# bug2.net
KiCad netlist of a schematic drawn in EAGLE
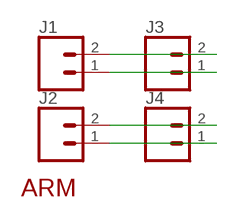
[diagram p0: schematic, sheet 1]

(export (version "E")
  (design (tool "Eeschema 10.0.6"))
  (components
    (comp (ref "J1")
      (value "CONN_02LOCK")
      (footprint "eagle-import:1X02_LOCK")
      (libsource (lib "eagle-import") (part "CONN_02LOCK"))
    )
    (comp (ref "J2")
      (value "CONN_02LOCK")
      (footprint "eagle-import:1X02_LOCK")
      (libsource (lib "eagle-import") (part "CONN_02LOCK"))
    )
    (comp (ref "J3")
      (value "CONN_02LOCK")
      (footprint "eagle-import:1X02_LOCK")
      (libsource (lib "eagle-import") (part "CONN_02LOCK"))
    )
    (comp (ref "J4")
      (value "CONN_02LOCK")
      (footprint "eagle-import:1X02_LOCK")
      (libsource (lib "eagle-import") (part "CONN_02LOCK"))
    )
    (comp (ref "U$1")
      (value "ARMBUG2")
      (footprint "eagle-import:BUG2")
      (libsource (lib "eagle-import") (part "ARMBUG2"))
    )
  )
  (nets
    (net (code "1") (name "Net-(J1-Pad1)") (class "Default")
      (node (ref "J1") (pin "1") (pinfunction "1_1") (pintype "passive"))
      (node (ref "J3") (pin "1") (pinfunction "1_1") (pintype "passive"))
    )
    (net (code "2") (name "Net-(J1-Pad2)") (class "Default")
      (node (ref "J1") (pin "2") (pinfunction "2_2") (pintype "passive"))
      (node (ref "J3") (pin "2") (pinfunction "2_2") (pintype "passive"))
    )
    (net (code "3") (name "Net-(J2-Pad1)") (class "Default")
      (node (ref "J2") (pin "1") (pinfunction "1_1") (pintype "passive"))
      (node (ref "J4") (pin "1") (pinfunction "1_1") (pintype "passive"))
    )
    (net (code "4") (name "Net-(J2-Pad2)") (class "Default")
      (node (ref "J2") (pin "2") (pinfunction "2_2") (pintype "passive"))
      (node (ref "J4") (pin "2") (pinfunction "2_2") (pintype "passive"))
    )
  )
)
